# BasicSwitch.net
KiCad netlist of a schematic drawn in EAGLE
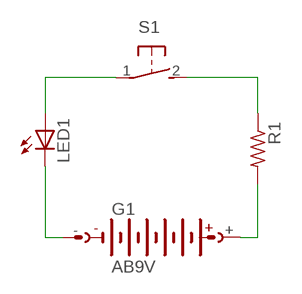
[diagram p0: schematic, sheet 1]

(export (version "E")
  (design (tool "Eeschema 10.0.6"))
  (components
    (comp (ref "G1")
      (value "AB9V")
      (footprint "eagle-import:AB9V")
      (libsource (lib "eagle-import") (part "AB9V"))
    )
    (comp (ref "LED1")
      (value "LEDCHIP-LED0805")
      (footprint "eagle-import:CHIP-LED0805")
      (libsource (lib "eagle-import") (part "LEDCHIP-LED0805"))
    )
    (comp (ref "R1")
      (value "R-US_M0805")
      (footprint "eagle-import:M0805")
      (libsource (lib "eagle-import") (part "R-US_M0805"))
    )
    (comp (ref "S1")
      (value "31-XXSKINNY")
      (footprint "eagle-import:B3F-31XX-SKINNIER")
      (libsource (lib "eagle-import") (part "31-XXSKINNY"))
    )
  )
  (nets
    (net (code "1") (name "Net-(G1-Pad+)") (class "Default")
      (node (ref "G1") (pin "+") (pinfunction "+_+") (pintype "passive"))
      (node (ref "R1") (pin "2") (pinfunction "2_2") (pintype "passive"))
    )
    (net (code "2") (name "Net-(G1-Pad-)") (class "Default")
      (node (ref "G1") (pin "-") (pinfunction "-_-") (pintype "passive"))
      (node (ref "LED1") (pin "C") (pinfunction "C_C") (pintype "passive"))
    )
    (net (code "3") (name "Net-(S1-P)") (class "Default")
      (node (ref "LED1") (pin "A") (pinfunction "A_A") (pintype "passive"))
      (node (ref "S1") (pin "1") (pinfunction "P_1") (pintype "passive"))
    )
    (net (code "4") (name "Net-(S1-S)") (class "Default")
      (node (ref "R1") (pin "1") (pinfunction "1_1") (pintype "passive"))
      (node (ref "S1") (pin "2") (pinfunction "S_2") (pintype "passive"))
    )
  )
)
